# Enclosure_100x68_HCP_A1.net
KiCad netlist of a schematic drawn in EAGLE
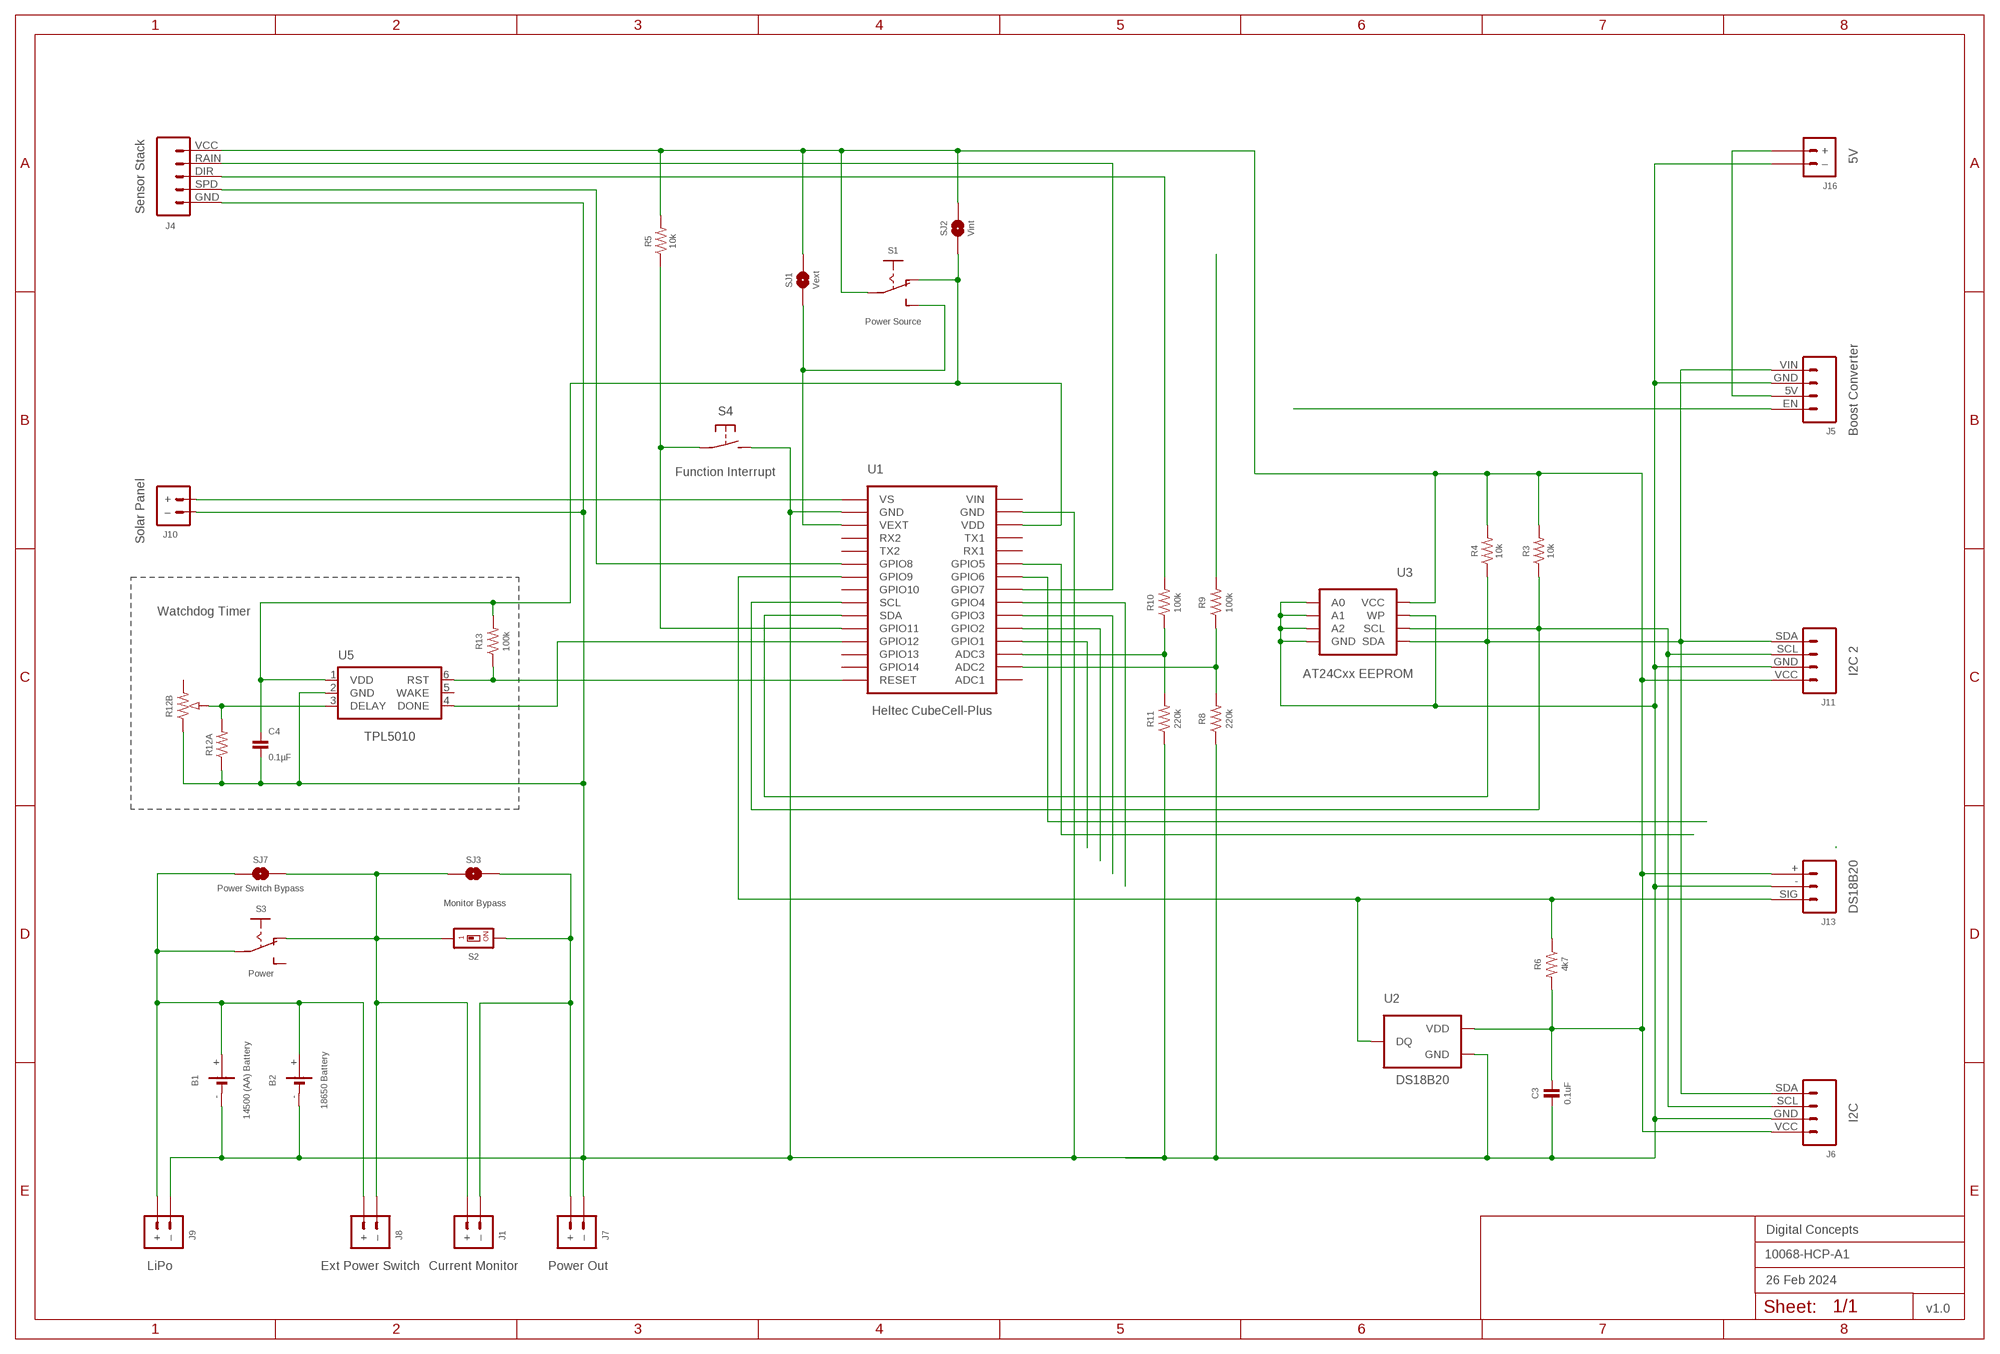
[diagram p0: schematic, sheet 1]

(export (version "E")
  (design (tool "Eeschema 10.0.6"))
  (components
    (comp (ref "B1")
      (value "14500 (AA) Battery")
      (footprint "eagle-import:BATTERY-14500")
      (libsource (lib "eagle-import") (part "BATTERY-HOLDER-14500(AA)"))
    )
    (comp (ref "B2")
      (value "18650 Battery")
      (footprint "eagle-import:BATTERY-18650")
      (libsource (lib "eagle-import") (part "BATTERY-HOLDER-18650"))
    )
    (comp (ref "C3")
      (value "0.1uF")
      (footprint "eagle-import:C0805")
      (libsource (lib "eagle-import") (part "CAPACITOR-0805"))
    )
    (comp (ref "C4")
      (value "0.1µF")
      (footprint "eagle-import:C0805")
      (libsource (lib "eagle-import") (part "CAPACITOR-0805"))
    )
    (comp (ref "J1")
      (value "Current Monitor")
      (footprint "eagle-import:JST-PH2.0-2-HORIZONTAL")
      (libsource (lib "eagle-import") (part "JST-PH2.0-2-HORIZONTALJST-PTH-2"))
    )
    (comp (ref "J4")
      (value "Sensor Stack")
      (footprint "eagle-import:JST-PH2.0-5-DUAL-WEATHER")
      (libsource (lib "eagle-import") (part "JST-PH2.0-5-DUAL-WEATHER"))
    )
    (comp (ref "J5")
      (value "Boost Converter")
      (footprint "eagle-import:CONN_04-FP6277")
      (libsource (lib "eagle-import") (part "HEADER-1X4-FP6277"))
    )
    (comp (ref "J6")
      (value "I2C")
      (footprint "eagle-import:CONN_04-I2C")
      (libsource (lib "eagle-import") (part "HEADER-1X4-I2C"))
    )
    (comp (ref "J7")
      (value "Power Out")
      (footprint "eagle-import:JST-GH1.25-2-HORIZONTAL")
      (libsource (lib "eagle-import") (part "JST-GH1.25-2-HORIZONTAL-POWER"))
    )
    (comp (ref "J8")
      (value "Ext Power Switch")
      (footprint "eagle-import:JST-PH2.0-2-DUAL-POWER")
      (libsource (lib "eagle-import") (part "JST-PH2.0-2-DUAL-POWERJST-PTH-2"))
    )
    (comp (ref "J9")
      (value "LiPo")
      (footprint "eagle-import:JST-PH2.0-2-HORIZONTAL-POWER@1")
      (libsource (lib "eagle-import") (part "JST-PH2.0-2-HORIZONTAL-POWERJST-PTH-2"))
    )
    (comp (ref "J10")
      (value "Solar Panel")
      (footprint "eagle-import:JST-PH2.0-2-VERTICAL=POWER")
      (libsource (lib "eagle-import") (part "JST-PH2.0-2-VERTICAL"))
    )
    (comp (ref "J11")
      (value "I2C 2")
      (footprint "eagle-import:JST-PH2.0-4-HORIZONTAL")
      (libsource (lib "eagle-import") (part "JST-PH2.0-I2C-MALE-HORIZONTAL"))
    )
    (comp (ref "J13")
      (value "DS18B20")
      (footprint "eagle-import:JST-PH2.0-3-HORIZONTAL-DS18B20")
      (libsource (lib "eagle-import") (part "JST-PH2.0-3-HORIZONTAL-DS18B20"))
    )
    (comp (ref "J16")
      (value "5V")
      (footprint "eagle-import:JST-PH2.0-2-HORIZONTAL-POWER")
      (libsource (lib "eagle-import") (part "JST-PH2.0-2-H-POWER"))
    )
    (comp (ref "R3")
      (value "10k")
      (footprint "eagle-import:R0805")
      (libsource (lib "eagle-import") (part "RESISTORR0805"))
    )
    (comp (ref "R4")
      (value "10k")
      (footprint "eagle-import:R0805")
      (libsource (lib "eagle-import") (part "RESISTORR0805"))
    )
    (comp (ref "R5")
      (value "10k")
      (footprint "eagle-import:R0805")
      (libsource (lib "eagle-import") (part "RESISTORR0805"))
    )
    (comp (ref "R6")
      (value "4k7")
      (footprint "eagle-import:R0805")
      (libsource (lib "eagle-import") (part "RESISTORR0805"))
    )
    (comp (ref "R8")
      (value "220k")
      (footprint "eagle-import:R0805")
      (libsource (lib "eagle-import") (part "RESISTORR0805"))
    )
    (comp (ref "R9")
      (value "100k")
      (footprint "eagle-import:R0805")
      (libsource (lib "eagle-import") (part "RESISTORR0805"))
    )
    (comp (ref "R10")
      (value "100k")
      (footprint "eagle-import:R0805")
      (libsource (lib "eagle-import") (part "RESISTORR0805"))
    )
    (comp (ref "R11")
      (value "220k")
      (footprint "eagle-import:R0805")
      (libsource (lib "eagle-import") (part "RESISTORR0805"))
    )
    (comp (ref "R12A")
      (value "RESISTORR0805")
      (footprint "eagle-import:R0805")
      (libsource (lib "eagle-import") (part "RESISTORR0805"))
    )
    (comp (ref "R12B")
      (value "RESISTOR-TRIMM-33-US")
      (footprint "eagle-import:RTRIM3_3")
      (libsource (lib "eagle-import") (part "RESISTOR-TRIMM-33-US"))
    )
    (comp (ref "R13")
      (value "100k")
      (footprint "eagle-import:R0805")
      (libsource (lib "eagle-import") (part "RESISTORR0805"))
    )
    (comp (ref "S1")
      (value "Power Source")
      (footprint "eagle-import:SWITCH-SPDT-SMT")
      (libsource (lib "eagle-import") (part "SWITCH-SLIDE-SPDT-SMT"))
    )
    (comp (ref "S2")
      (value "Monitor Bypass")
      (footprint "eagle-import:SMD-001")
      (libsource (lib "eagle-import") (part "SWITCH-DIP-SWS001"))
    )
    (comp (ref "S3")
      (value "Power")
      (footprint "eagle-import:SWITCH-SPDT-PTH")
      (libsource (lib "eagle-import") (part "SWITCH-SLIDE-SPDT-PTH"))
    )
    (comp (ref "S4")
      (value "Function Interrupt")
      (footprint "eagle-import:SWITCH-2-PAD")
      (libsource (lib "eagle-import") (part "SWITCH-MOMENTARY-2-PIN"))
    )
    (comp (ref "SJ1")
      (value "Vext")
      (footprint "eagle-import:SJ")
      (libsource (lib "eagle-import") (part "SJ"))
    )
    (comp (ref "SJ2")
      (value "Vint")
      (footprint "eagle-import:SJ-VIA-12")
      (libsource (lib "eagle-import") (part "SJ-V-12"))
    )
    (comp (ref "SJ3")
      (value "Monitor")
      (footprint "eagle-import:SJ")
      (libsource (lib "eagle-import") (part "SJ"))
    )
    (comp (ref "SJ7")
      (value "Power Switch Bypass")
      (footprint "eagle-import:SJ")
      (libsource (lib "eagle-import") (part "SJ"))
    )
    (comp (ref "U1")
      (value "Heltec CubeCell-Plus")
      (footprint "eagle-import:HELTEC-CUBECELL=PLUS-X")
      (libsource (lib "eagle-import") (part "HELTEC-CUBECELL-PLUS-X"))
    )
    (comp (ref "U2")
      (value "DS18B20")
      (footprint "eagle-import:TO-92")
      (fields (field (name "MF") "Maxim Integrated"))
      (libsource (lib "eagle-import") (part "THERMOMETER-DS18B20"))
    )
    (comp (ref "U3")
      (value "AT24Cxx EEPROM")
      (footprint "eagle-import:SOP-8")
      (libsource (lib "eagle-import") (part "AT24CXX-EEPROM"))
    )
    (comp (ref "U5")
      (value "TPL5010")
      (footprint "eagle-import:SOT-23-6")
      (libsource (lib "eagle-import") (part "TPL5010DDCR"))
    )
  )
  (nets
    (net (code "1") (name "/VIN") (class "Default")
      (node (ref "U1") (pin "VIN") (pinfunction "VIN_VIN") (pintype "power_in"))
    )
    (net (code "2") (name "Net-(J1-+)") (class "Default")
      (node (ref "J1") (pin "1") (pinfunction "+_1") (pintype "power_in"))
      (node (ref "J8") (pin "-") (pinfunction "–_-") (pintype "power_in"))
      (node (ref "S2") (pin "1") (pinfunction "1_1") (pintype "passive"))
      (node (ref "S3") (pin "1") (pinfunction "O_1") (pintype "passive"))
      (node (ref "SJ3") (pin "2") (pinfunction "2_2") (pintype "passive"))
      (node (ref "SJ7") (pin "1") (pinfunction "1_1") (pintype "passive"))
    )
    (net (code "3") (name "Net-(J1-–)") (class "Default")
      (node (ref "J1") (pin "2") (pinfunction "–_2") (pintype "power_in"))
      (node (ref "J7") (pin "+") (pinfunction "+_+") (pintype "power_in"))
      (node (ref "S2") (pin "2") (pinfunction "2_2") (pintype "passive"))
      (node (ref "SJ3") (pin "1") (pinfunction "1_1") (pintype "passive"))
    )
    (net (code "4") (name "Net-(J4-2)") (class "Default")
      (node (ref "J4") (pin "RAIN") (pinfunction "2_RAIN") (pintype "passive"))
      (node (ref "U1") (pin "GPIO7") (pinfunction "GPIO7_GPIO7") (pintype "bidirectional"))
    )
    (net (code "5") (name "Net-(J4-3)") (class "Default")
      (node (ref "J4") (pin "DIR") (pinfunction "3_DIR") (pintype "passive"))
      (node (ref "R10") (pin "2") (pinfunction "2_2") (pintype "passive"))
    )
    (net (code "6") (name "Net-(J4-4)") (class "Default")
      (node (ref "J4") (pin "SPD") (pinfunction "4_SPD") (pintype "passive"))
      (node (ref "U1") (pin "GPIO8") (pinfunction "GPIO8_GPIO8") (pintype "bidirectional"))
    )
    (net (code "7") (name "Net-(J5-2)") (class "Default")
      (node (ref "J16") (pin "+") (pinfunction "+_+") (pintype "power_in"))
      (node (ref "J5") (pin "5V") (pinfunction "2_5V") (pintype "passive"))
    )
    (net (code "8") (name "Net-(J10-Pad+)") (class "Default")
      (node (ref "J10") (pin "+") (pinfunction "+_+") (pintype "power_in"))
      (node (ref "U1") (pin "VS") (pinfunction "VS_VS") (pintype "power_in"))
    )
    (net (code "9") (name "Net-(J10-–)") (class "Default")
      (node (ref "B1") (pin "-") (pinfunction "-_-") (pintype "power_in"))
      (node (ref "B2") (pin "-") (pinfunction "-_-") (pintype "power_in"))
      (node (ref "C3") (pin "2") (pinfunction "2_2") (pintype "passive"))
      (node (ref "C4") (pin "2") (pinfunction "2_2") (pintype "passive"))
      (node (ref "J10") (pin "-") (pinfunction "–_-") (pintype "power_in"))
      (node (ref "J11") (pin "GND") (pinfunction "2_GND") (pintype "passive"))
      (node (ref "J13") (pin "-") (pinfunction "2_-") (pintype "passive"))
      (node (ref "J16") (pin "-") (pinfunction "–_-") (pintype "power_in"))
      (node (ref "J4") (pin "GND") (pinfunction "5_GND") (pintype "passive"))
      (node (ref "J5") (pin "GND") (pinfunction "3_GND") (pintype "passive"))
      (node (ref "J6") (pin "GND") (pinfunction "2_GND") (pintype "passive"))
      (node (ref "J7") (pin "-") (pinfunction "–_-") (pintype "power_in"))
      (node (ref "J9") (pin "-") (pinfunction "–_-") (pintype "power_in"))
      (node (ref "R11") (pin "1") (pinfunction "1_1") (pintype "passive"))
      (node (ref "R12A") (pin "1") (pinfunction "1_1") (pintype "passive"))
      (node (ref "R12B") (pin "1") (pinfunction "A_1") (pintype "passive"))
      (node (ref "R8") (pin "1") (pinfunction "1_1") (pintype "passive"))
      (node (ref "S4") (pin "P$2") (pinfunction "S_P$2") (pintype "passive"))
      (node (ref "U1") (pin "GND@14") (pinfunction "GND_GND@14") (pintype "power_in"))
      (node (ref "U1") (pin "GND@17") (pinfunction "GND_GND@17") (pintype "power_in"))
      (node (ref "U2") (pin "1") (pinfunction "GND_1") (pintype "power_in"))
      (node (ref "U3") (pin "P$1") (pinfunction "A0_P$1") (pintype "bidirectional"))
      (node (ref "U3") (pin "P$2") (pinfunction "A1_P$2") (pintype "bidirectional"))
      (node (ref "U3") (pin "P$3") (pinfunction "A2_P$3") (pintype "bidirectional"))
      (node (ref "U3") (pin "P$4") (pinfunction "GND_P$4") (pintype "bidirectional"))
      (node (ref "U3") (pin "P$7") (pinfunction "WP_P$7") (pintype "bidirectional"))
      (node (ref "U5") (pin "2") (pinfunction "GND_2") (pintype "power_in"))
    )
    (net (code "10") (name "Net-(J11-1)") (class "Default")
      (node (ref "C3") (pin "1") (pinfunction "1_1") (pintype "passive"))
      (node (ref "J11") (pin "VCC") (pinfunction "1_VCC") (pintype "passive"))
      (node (ref "J13") (pin "+") (pinfunction "3_+") (pintype "passive"))
      (node (ref "J4") (pin "VCC") (pinfunction "1_VCC") (pintype "passive"))
      (node (ref "J6") (pin "VCC") (pinfunction "1_VCC") (pintype "passive"))
      (node (ref "R3") (pin "2") (pinfunction "2_2") (pintype "passive"))
      (node (ref "R4") (pin "2") (pinfunction "2_2") (pintype "passive"))
      (node (ref "R5") (pin "2") (pinfunction "2_2") (pintype "passive"))
      (node (ref "R6") (pin "2") (pinfunction "2_2") (pintype "passive"))
      (node (ref "S1") (pin "2") (pinfunction "P_2") (pintype "passive"))
      (node (ref "SJ1") (pin "2") (pinfunction "2_2") (pintype "passive"))
      (node (ref "SJ2") (pin "2") (pinfunction "2_2") (pintype "passive"))
      (node (ref "SJ2") (pin "2@V") (pinfunction "2_2@V") (pintype "passive"))
      (node (ref "U2") (pin "3") (pinfunction "VDD_3") (pintype "power_in"))
      (node (ref "U3") (pin "P$8") (pinfunction "VCC_P$8") (pintype "bidirectional"))
    )
    (net (code "11") (name "Net-(J11-3)") (class "Default")
      (node (ref "J11") (pin "SCL") (pinfunction "3_SCL") (pintype "passive"))
      (node (ref "J6") (pin "SCL") (pinfunction "3_SCL") (pintype "passive"))
      (node (ref "R3") (pin "1") (pinfunction "1_1") (pintype "passive"))
      (node (ref "U1") (pin "SCL") (pinfunction "SCL_SCL") (pintype "bidirectional"))
      (node (ref "U3") (pin "P$6") (pinfunction "SCL_P$6") (pintype "bidirectional"))
    )
    (net (code "12") (name "Net-(J11-4)") (class "Default")
      (node (ref "J11") (pin "SDA") (pinfunction "4_SDA") (pintype "passive"))
      (node (ref "J5") (pin "VIN") (pinfunction "4_VIN") (pintype "passive"))
      (node (ref "J6") (pin "SDA") (pinfunction "4_SDA") (pintype "passive"))
      (node (ref "R4") (pin "1") (pinfunction "1_1") (pintype "passive"))
      (node (ref "U1") (pin "SDA") (pinfunction "SDA_SDA") (pintype "bidirectional"))
      (node (ref "U3") (pin "P$5") (pinfunction "SDA_P$5") (pintype "bidirectional"))
    )
    (net (code "13") (name "Net-(J13-1)") (class "Default")
      (node (ref "J13") (pin "SIG") (pinfunction "1_SIG") (pintype "passive"))
      (node (ref "R6") (pin "1") (pinfunction "1_1") (pintype "passive"))
      (node (ref "U1") (pin "GPIO9") (pinfunction "GPIO9_GPIO9") (pintype "bidirectional"))
      (node (ref "U2") (pin "2") (pinfunction "DQ_2") (pintype "bidirectional"))
    )
    (net (code "14") (name "Net-(R8-Pad2)") (class "Default")
      (node (ref "R8") (pin "2") (pinfunction "2_2") (pintype "passive"))
      (node (ref "R9") (pin "1") (pinfunction "1_1") (pintype "passive"))
      (node (ref "U1") (pin "ADC2") (pinfunction "ADC2_ADC2") (pintype "bidirectional"))
    )
    (net (code "15") (name "Net-(R10-Pad1)") (class "Default")
      (node (ref "R10") (pin "1") (pinfunction "1_1") (pintype "passive"))
      (node (ref "R11") (pin "2") (pinfunction "2_2") (pintype "passive"))
      (node (ref "U1") (pin "ADC3") (pinfunction "ADC3_ADC3") (pintype "bidirectional"))
    )
    (net (code "16") (name "Net-(R12B-S)") (class "Default")
      (node (ref "R12A") (pin "2") (pinfunction "2_2") (pintype "passive"))
      (node (ref "R12B") (pin "2") (pinfunction "S_2") (pintype "passive"))
      (node (ref "U5") (pin "3") (pinfunction "DELAY_3") (pintype "input"))
    )
    (net (code "17") (name "Net-(S1-O)") (class "Default")
      (node (ref "C4") (pin "1") (pinfunction "1_1") (pintype "passive"))
      (node (ref "R13") (pin "2") (pinfunction "2_2") (pintype "passive"))
      (node (ref "S1") (pin "1") (pinfunction "O_1") (pintype "passive"))
      (node (ref "SJ2") (pin "1") (pinfunction "1_1") (pintype "passive"))
      (node (ref "SJ2") (pin "1@V") (pinfunction "1_1@V") (pintype "passive"))
      (node (ref "U1") (pin "VDD") (pinfunction "VDD_VDD") (pintype "power_in"))
      (node (ref "U5") (pin "1") (pinfunction "VDD_1") (pintype "power_in"))
    )
    (net (code "18") (name "Net-(S1-S)") (class "Default")
      (node (ref "S1") (pin "3") (pinfunction "S_3") (pintype "passive"))
      (node (ref "SJ1") (pin "1") (pinfunction "1_1") (pintype "passive"))
      (node (ref "U1") (pin "VEXT") (pinfunction "VEXT_VEXT") (pintype "power_in"))
    )
    (net (code "19") (name "Net-(S3-P)") (class "Default")
      (node (ref "B1") (pin "+") (pinfunction "+_+") (pintype "power_in"))
      (node (ref "B2") (pin "+") (pinfunction "+_+") (pintype "power_in"))
      (node (ref "J8") (pin "+") (pinfunction "+_+") (pintype "power_in"))
      (node (ref "J9") (pin "+") (pinfunction "+_+") (pintype "power_in"))
      (node (ref "S3") (pin "2") (pinfunction "P_2") (pintype "passive"))
      (node (ref "SJ7") (pin "2") (pinfunction "2_2") (pintype "passive"))
    )
    (net (code "20") (name "Net-(S4-P)") (class "Default")
      (node (ref "R5") (pin "1") (pinfunction "1_1") (pintype "passive"))
      (node (ref "S4") (pin "P$1") (pinfunction "P_P$1") (pintype "passive"))
      (node (ref "U1") (pin "GPIO11") (pinfunction "GPIO11_GPIO11") (pintype "bidirectional"))
    )
    (net (code "21") (name "Net-(U1-RESET)") (class "Default")
      (node (ref "R13") (pin "1") (pinfunction "1_1") (pintype "passive"))
      (node (ref "U1") (pin "RST") (pinfunction "RESET_RST") (pintype "bidirectional"))
      (node (ref "U5") (pin "6") (pinfunction "RST_6") (pintype "output"))
    )
    (net (code "22") (name "Net-(U5-DONE)") (class "Default")
      (node (ref "U1") (pin "GPIO12") (pinfunction "GPIO12_GPIO12") (pintype "bidirectional"))
      (node (ref "U5") (pin "4") (pinfunction "DONE_4") (pintype "input"))
    )
    (net (code "23") (name "unconnected-(J5-1-PadEN)") (class "Default")
      (node (ref "J5") (pin "EN") (pinfunction "1_EN") (pintype "passive"))
    )
    (net (code "24") (name "unconnected-(R9-Pad2)") (class "Default")
      (node (ref "R9") (pin "2") (pinfunction "2_2") (pintype "passive"))
    )
    (net (code "25") (name "unconnected-(R12B-E-Pad3)") (class "Default")
      (node (ref "R12B") (pin "3") (pinfunction "E_3") (pintype "passive"))
    )
    (net (code "26") (name "unconnected-(S3-S-Pad3)") (class "Default")
      (node (ref "S3") (pin "3") (pinfunction "S_3") (pintype "passive"))
    )
    (net (code "27") (name "unconnected-(U1-PadADC1)") (class "Default")
      (node (ref "U1") (pin "ADC1") (pinfunction "ADC1_ADC1") (pintype "bidirectional"))
    )
    (net (code "28") (name "unconnected-(U1-PadGPIO1)") (class "Default")
      (node (ref "U1") (pin "GPIO1") (pinfunction "GPIO1_GPIO1") (pintype "bidirectional"))
    )
    (net (code "29") (name "unconnected-(U1-PadGPIO2)") (class "Default")
      (node (ref "U1") (pin "GPIO2") (pinfunction "GPIO2_GPIO2") (pintype "bidirectional"))
    )
    (net (code "30") (name "unconnected-(U1-PadGPIO3)") (class "Default")
      (node (ref "U1") (pin "GPIO3") (pinfunction "GPIO3_GPIO3") (pintype "bidirectional"))
    )
    (net (code "31") (name "unconnected-(U1-PadGPIO4)") (class "Default")
      (node (ref "U1") (pin "GPIO4") (pinfunction "GPIO4_GPIO4") (pintype "bidirectional"))
    )
    (net (code "32") (name "unconnected-(U1-PadGPIO5)") (class "Default")
      (node (ref "U1") (pin "GPIO5") (pinfunction "GPIO5_GPIO5") (pintype "bidirectional"))
    )
    (net (code "33") (name "unconnected-(U1-PadGPIO6)") (class "Default")
      (node (ref "U1") (pin "GPIO6") (pinfunction "GPIO6_GPIO6") (pintype "bidirectional"))
    )
    (net (code "34") (name "unconnected-(U1-PadGPIO10)") (class "Default")
      (node (ref "U1") (pin "GPIO10") (pinfunction "GPIO10_GPIO10") (pintype "bidirectional"))
    )
    (net (code "35") (name "unconnected-(U1-PadGPIO13)") (class "Default")
      (node (ref "U1") (pin "GPIO13") (pinfunction "GPIO13_GPIO13") (pintype "bidirectional"))
    )
    (net (code "36") (name "unconnected-(U1-PadGPIO14)") (class "Default")
      (node (ref "U1") (pin "GPIO14") (pinfunction "GPIO14_GPIO14") (pintype "bidirectional"))
    )
    (net (code "37") (name "unconnected-(U1-PadRX1)") (class "Default")
      (node (ref "U1") (pin "RX1") (pinfunction "RX1_RX1") (pintype "bidirectional"))
    )
    (net (code "38") (name "unconnected-(U1-PadRX2)") (class "Default")
      (node (ref "U1") (pin "RX2") (pinfunction "RX2_RX2") (pintype "bidirectional"))
    )
    (net (code "39") (name "unconnected-(U1-PadTX1)") (class "Default")
      (node (ref "U1") (pin "TX1") (pinfunction "TX1_TX1") (pintype "bidirectional"))
    )
    (net (code "40") (name "unconnected-(U1-PadTX2)") (class "Default")
      (node (ref "U1") (pin "TX2") (pinfunction "TX2_TX2") (pintype "bidirectional"))
    )
    (net (code "41") (name "unconnected-(U5-WAKE-Pad5)") (class "Default")
      (node (ref "U5") (pin "5") (pinfunction "WAKE_5") (pintype "output"))
    )
  )
)
